# TMS320F280049CPZS.net
KiCad netlist of a schematic drawn in Altium Designer
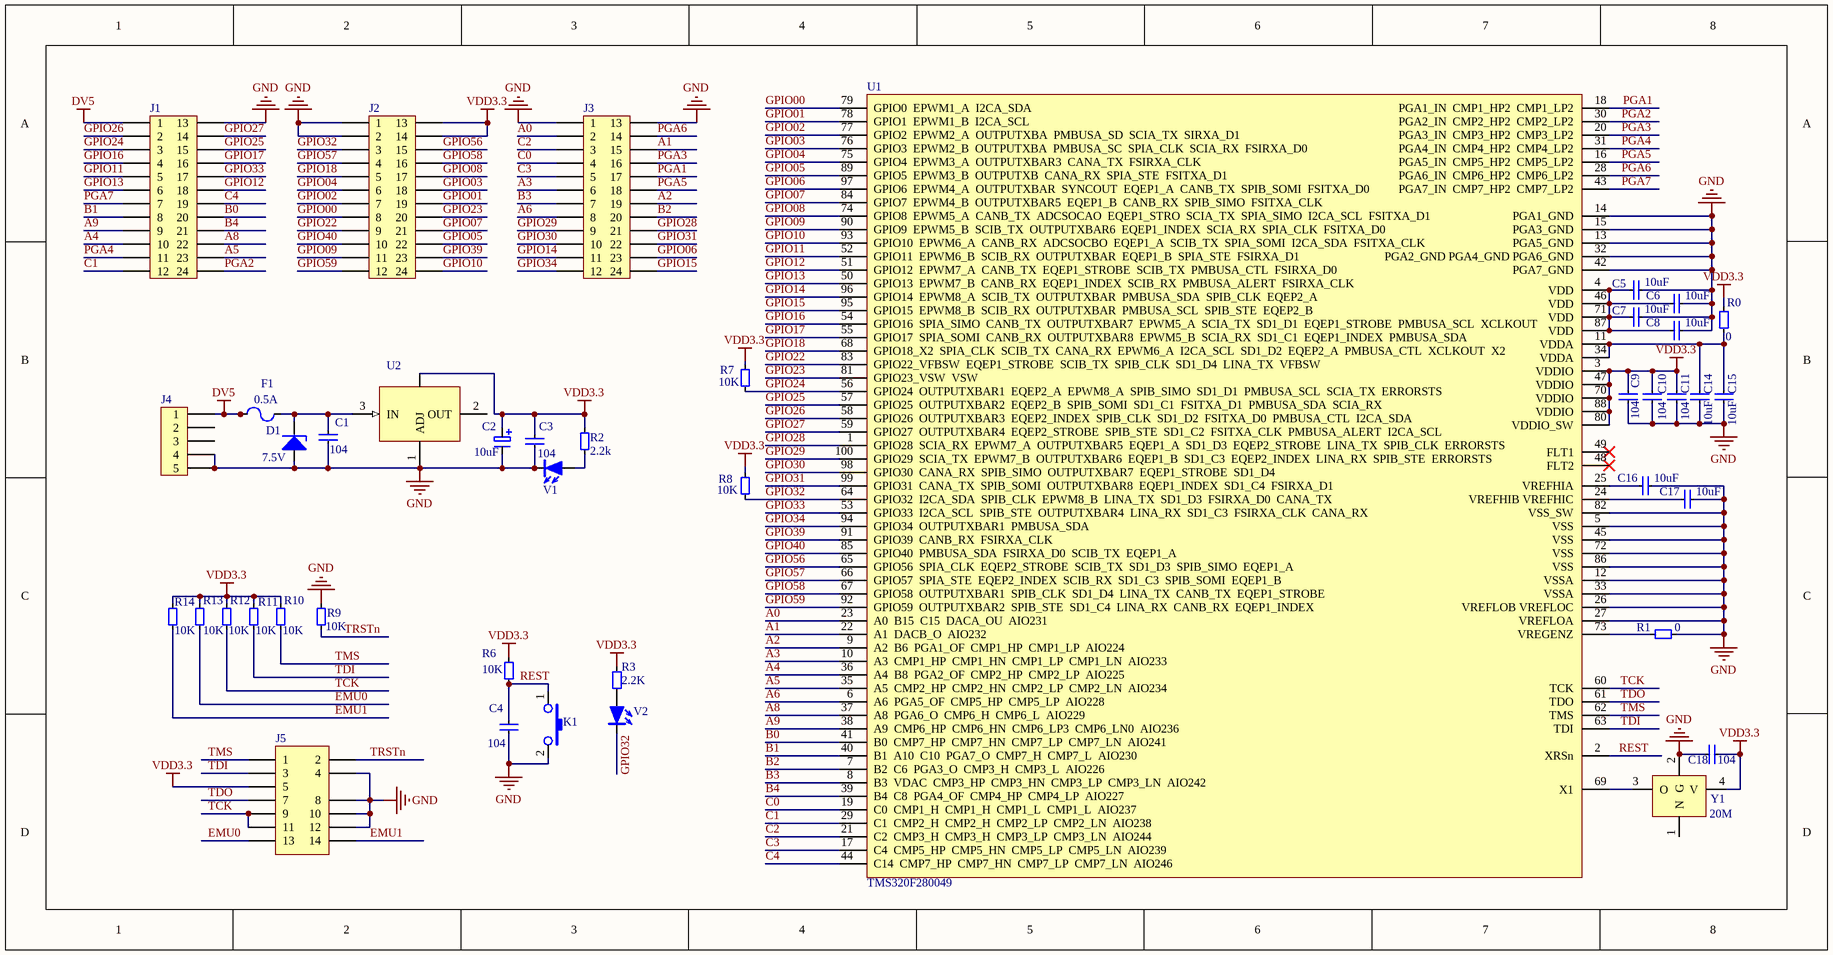
[diagram p0: TMS320F280049CPZS.SchDoc]

(export (version "E")
  (design (tool "Eeschema 10.0.6"))
  (components
    (comp (ref "C1") (value "104") (footprint "0805_C_M") (libsource (lib "电容系列") (part "C3")))
    (comp (ref "C2") (value "10uF") (footprint "CE3528") (libsource (lib "电容系列") (part "E3")))
    (comp (ref "C3") (value "104") (footprint "0805_C_M") (libsource (lib "电容系列") (part "C3")))
    (comp (ref "C4") (value "104") (footprint "0805_C_M") (libsource (lib "电容系列") (part "C3")))
    (comp (ref "C5") (value "10uF") (footprint "0805_C_M") (libsource (lib "电容系列") (part "C3")))
    (comp (ref "C6") (value "10uF") (footprint "0805_C_M") (libsource (lib "电容系列") (part "C3")))
    (comp (ref "C7") (value "10uF") (footprint "0805_C_M") (libsource (lib "电容系列") (part "C3")))
    (comp (ref "C8") (value "10uF") (footprint "0805_C_M") (libsource (lib "电容系列") (part "C3")))
    (comp (ref "C9") (value "104") (footprint "0805_C_M") (libsource (lib "电容系列") (part "C3")))
    (comp (ref "C10") (value "104") (footprint "0805_C_M") (libsource (lib "电容系列") (part "C3")))
    (comp (ref "C11") (value "104") (footprint "0805_C_M") (libsource (lib "电容系列") (part "C3")))
    (comp (ref "C14") (value "10uF") (footprint "0805_C_M") (libsource (lib "电容系列") (part "C3")))
    (comp (ref "C15") (value "10uF") (footprint "0805_C_M") (libsource (lib "电容系列") (part "C3")))
    (comp (ref "C16") (value "10uF") (footprint "0805_C_M") (libsource (lib "电容系列") (part "C3")))
    (comp (ref "C17") (value "10uF") (footprint "0805_C_M") (libsource (lib "电容系列") (part "C3")))
    (comp (ref "C18") (value "104") (footprint "0805_C_M") (libsource (lib "电容系列") (part "C3")))
    (comp (ref "D1") (value "7.5V") (footprint "1206D") (libsource (lib "二极管") (part "D4")))
    (comp (ref "F1") (value "0.5A") (footprint "1812F") (libsource (lib "常用库") (part "FUSE1")))
    (comp (ref "J1") (value "CON24") (footprint "CON24_2.54") (libsource (lib "DIP_SIP") (part "CON24")))
    (comp (ref "J2") (value "CON24") (footprint "CON24_2.54") (libsource (lib "DIP_SIP") (part "CON24")))
    (comp (ref "J3") (value "CON24") (footprint "CON24_2.54") (libsource (lib "DIP_SIP") (part "CON24")))
    (comp (ref "J4") (value "SIP5") (footprint "MINIUSB-S") (libsource (lib "DIP_SIP") (part "SIP5")))
    (comp (ref "J5")
      (value "Header 7X2")
      (footprint "JTAG14")
      (description "Header, 7-Pin, Dual row")
      (fields (field (name "PUBLISHER") "Altium Limited"))
      (libsource (lib "myproject") (part "Header 7X2"))
    )
    (comp (ref "K1") (value "KEY1") (libsource (lib "Common") (part "KEY1")))
    (comp (ref "R0") (value "0") (footprint "0805_R_M") (libsource (lib "电阻系列") (part "R3")))
    (comp (ref "R1") (value "0") (footprint "0805_R_M") (libsource (lib "电阻系列") (part "R3")))
    (comp (ref "R2") (value "2.2k") (footprint "0805_R_M") (libsource (lib "电阻系列") (part "R3")))
    (comp (ref "R3") (value "2.2K") (footprint "0805_R_M") (libsource (lib "电阻系列") (part "R3")))
    (comp (ref "R6") (value "10K") (footprint "0805_R_M") (libsource (lib "电阻系列") (part "R3")))
    (comp (ref "R7") (value "10K") (footprint "0805_R_M") (libsource (lib "电阻系列") (part "R3")))
    (comp (ref "R8") (value "10K") (footprint "0805_R_M") (libsource (lib "电阻系列") (part "R3")))
    (comp (ref "R9") (value "10K") (footprint "0805_R_M") (libsource (lib "电阻系列") (part "R3")))
    (comp (ref "R10") (value "10K") (footprint "0805_R_M") (libsource (lib "电阻系列") (part "R3")))
    (comp (ref "R11") (value "10K") (footprint "0805_R_M") (libsource (lib "电阻系列") (part "R3")))
    (comp (ref "R12") (value "10K") (footprint "0805_R_M") (libsource (lib "电阻系列") (part "R3")))
    (comp (ref "R13") (value "10K") (footprint "0805_R_M") (libsource (lib "电阻系列") (part "R3")))
    (comp (ref "R14") (value "10K") (footprint "0805_R_M") (libsource (lib "电阻系列") (part "R3")))
    (comp (ref "U1")
      (value "TMS320F280049")
      (footprint "STM32F407VGT6")
      (libsource (lib "IC-ZB") (part "TMS320F280049"))
    )
    (comp (ref "U2") (value "AMS1117-3.3") (footprint "LM1117") (libsource (lib "电源（专用）") (part "1117")))
    (comp (ref "V1") (value "LED") (footprint "0805D") (libsource (lib "发光管、数码管") (part "LED2")))
    (comp (ref "V2") (value "LED2") (footprint "0805D") (libsource (lib "发光管、数码管") (part "LED2")))
    (comp (ref "Y1") (value "20M") (footprint "OSC5070") (libsource (lib "常用库") (part "CY2_有源")))
  )
  (nets
    (net (code "1") (name "/A0") (class "Default")
      (node (ref "J3") (pin "2") (pinfunction "2_2") (pintype "passive"))
      (node (ref "U1") (pin "23") (pinfunction "A0__B15__C15__DACA_OU__AIO231_23") (pintype "passive"))
    )
    (net (code "2") (name "/A1") (class "Default")
      (node (ref "J3") (pin "15") (pinfunction "15_15") (pintype "passive"))
      (node (ref "U1") (pin "22") (pinfunction "A1__DACB_O__AIO232_22") (pintype "passive"))
    )
    (net (code "3") (name "/A2") (class "Default")
      (node (ref "J3") (pin "19") (pinfunction "19_19") (pintype "passive"))
      (node (ref "U1") (pin "9") (pinfunction "A2__B6__PGA1_OF__CMP1_HP__CMP1_LP__AIO224_9") (pintype "passive"))
    )
    (net (code "4") (name "/A3") (class "Default")
      (node (ref "J3") (pin "6") (pinfunction "6_6") (pintype "passive"))
      (node (ref "U1") (pin "10") (pinfunction "A3__CMP1_HP__CMP1_HN__CMP1_LP__CMP1_LN__AIO233_10") (pintype "passive"))
    )
    (net (code "5") (name "/A4") (class "Default")
      (node (ref "J1") (pin "10") (pinfunction "10_10") (pintype "passive"))
      (node (ref "U1") (pin "36") (pinfunction "A4__B8__PGA2_OF__CMP2_HP__CMP2_LP__AIO225_36") (pintype "passive"))
    )
    (net (code "6") (name "/A5") (class "Default")
      (node (ref "J1") (pin "23") (pinfunction "23_23") (pintype "passive"))
      (node (ref "U1") (pin "35") (pinfunction "A5__CMP2_HP__CMP2_HN__CMP2_LP__CMP2_LN__AIO234_35") (pintype "passive"))
    )
    (net (code "7") (name "/A6") (class "Default")
      (node (ref "J3") (pin "8") (pinfunction "8_8") (pintype "passive"))
      (node (ref "U1") (pin "6") (pinfunction "A6__PGA5_OF__CMP5_HP__CMP5_LP__AIO228_6") (pintype "passive"))
    )
    (net (code "8") (name "/A8") (class "Default")
      (node (ref "J1") (pin "22") (pinfunction "22_22") (pintype "passive"))
      (node (ref "U1") (pin "37") (pinfunction "A8__PGA6_O__CMP6_H__CMP6_L__AIO229_37") (pintype "passive"))
    )
    (net (code "9") (name "/A9") (class "Default")
      (node (ref "J1") (pin "9") (pinfunction "9_9") (pintype "passive"))
      (node (ref "U1") (pin "38") (pinfunction "A9__CMP6_HP__CMP6_HN__CMP6_LP3__CMP6_LN0__AIO236_38") (pintype "passive"))
    )
    (net (code "10") (name "/B0") (class "Default")
      (node (ref "J1") (pin "20") (pinfunction "20_20") (pintype "passive"))
      (node (ref "U1") (pin "41") (pinfunction "B0__CMP7_HP__CMP7_HN__CMP7_LP__CMP7_LN__AIO241_41") (pintype "passive"))
    )
    (net (code "11") (name "/B1") (class "Default")
      (node (ref "J1") (pin "8") (pinfunction "8_8") (pintype "passive"))
      (node (ref "U1") (pin "40") (pinfunction "B1__A10__C10__PGA7_O__CMP7_H__CMP7_L__AIO230_40") (pintype "passive"))
    )
    (net (code "12") (name "/B2") (class "Default")
      (node (ref "J3") (pin "20") (pinfunction "20_20") (pintype "passive"))
      (node (ref "U1") (pin "7") (pinfunction "B2__C6__PGA3_O__CMP3_H__CMP3_L__AIO226_7") (pintype "passive"))
    )
    (net (code "13") (name "/B3") (class "Default")
      (node (ref "J3") (pin "7") (pinfunction "7_7") (pintype "passive"))
      (node (ref "U1") (pin "8") (pinfunction "B3__VDAC__CMP3_HP__CMP3_HN__CMP3_LP__CMP3_LN__AIO242_8") (pintype "passive"))
    )
    (net (code "14") (name "/B4") (class "Default")
      (node (ref "J1") (pin "21") (pinfunction "21_21") (pintype "passive"))
      (node (ref "U1") (pin "39") (pinfunction "B4__C8__PGA4_OF__CMP4_HP__CMP4_LP__AIO227_39") (pintype "passive"))
    )
    (net (code "15") (name "/C0") (class "Default")
      (node (ref "J3") (pin "4") (pinfunction "4_4") (pintype "passive"))
      (node (ref "U1") (pin "19") (pinfunction "C0__CMP1_H__CMP1_H__CMP1_L__CMP1_L__AIO237_19") (pintype "passive"))
    )
    (net (code "16") (name "/C1") (class "Default")
      (node (ref "J1") (pin "12") (pinfunction "12_12") (pintype "passive"))
      (node (ref "U1") (pin "29") (pinfunction "C1__CMP2_H__CMP2_H__CMP2_LP__CMP2_LN__AIO238_29") (pintype "passive"))
    )
    (net (code "17") (name "/C2") (class "Default")
      (node (ref "J3") (pin "3") (pinfunction "3_3") (pintype "passive"))
      (node (ref "U1") (pin "21") (pinfunction "C2__CMP3_H__CMP3_H__CMP3_LP__CMP3_LN__AIO244_21") (pintype "passive"))
    )
    (net (code "18") (name "/C3") (class "Default")
      (node (ref "J3") (pin "5") (pinfunction "5_5") (pintype "passive"))
      (node (ref "U1") (pin "17") (pinfunction "C4__CMP5_HP__CMP5_HN__CMP5_LP__CMP5_LN__AIO239_17") (pintype "passive"))
    )
    (net (code "19") (name "/C4") (class "Default")
      (node (ref "J1") (pin "19") (pinfunction "19_19") (pintype "passive"))
      (node (ref "U1") (pin "44") (pinfunction "C14__CMP7_HP__CMP7_HN__CMP7_LP__CMP7_LN__AIO246_44") (pintype "passive"))
    )
    (net (code "20") (name "/EMU0") (class "Default")
      (node (ref "J5") (pin "13") (pinfunction "13_13") (pintype "passive"))
      (node (ref "R13") (pin "1") (pinfunction "1_1") (pintype "passive"))
    )
    (net (code "21") (name "/EMU1") (class "Default")
      (node (ref "J5") (pin "14") (pinfunction "14_14") (pintype "passive"))
      (node (ref "R14") (pin "1") (pinfunction "1_1") (pintype "passive"))
    )
    (net (code "22") (name "/GPIO00") (class "Default")
      (node (ref "J2") (pin "8") (pinfunction "8_8") (pintype "passive"))
      (node (ref "U1") (pin "79") (pinfunction "GPIO0__EPWM1_A__I2CA_SDA_79") (pintype "passive"))
    )
    (net (code "23") (name "/GPIO01") (class "Default")
      (node (ref "J2") (pin "19") (pinfunction "19_19") (pintype "passive"))
      (node (ref "U1") (pin "78") (pinfunction "GPIO1__EPWM1_B__I2CA_SCL_78") (pintype "passive"))
    )
    (net (code "24") (name "/GPIO02") (class "Default")
      (node (ref "J2") (pin "7") (pinfunction "7_7") (pintype "passive"))
      (node (ref "U1") (pin "77") (pinfunction "GPIO2__EPWM2_A__OUTPUTXBA__PMBUSA_SD__SCIA_TX__SIRXA_D1_77") (pintype "passive"))
    )
    (net (code "25") (name "/GPIO03") (class "Default")
      (node (ref "J2") (pin "18") (pinfunction "18_18") (pintype "passive"))
      (node (ref "U1") (pin "76") (pinfunction "GPIO3__EPWM2_B__OUTPUTXBA__PMBUSA_SC__SPIA_CLK__SCIA_RX__FSIRXA_D0_76") (pintype "passive"))
    )
    (net (code "26") (name "/GPIO04") (class "Default")
      (node (ref "J2") (pin "6") (pinfunction "6_6") (pintype "passive"))
      (node (ref "U1") (pin "75") (pinfunction "GPIO4__EPWM3_A__OUTPUTXBAR3__CANA_TX__FSIRXA_CLK_75") (pintype "passive"))
    )
    (net (code "27") (name "/GPIO05") (class "Default")
      (node (ref "J2") (pin "22") (pinfunction "22_22") (pintype "passive"))
      (node (ref "U1") (pin "89") (pinfunction "GPIO5__EPWM3_B__OUTPUTXB__CANA_RX__SPIA_STE__FSITXA_D1_89") (pintype "passive"))
    )
    (net (code "28") (name "/GPIO06") (class "Default")
      (node (ref "J3") (pin "23") (pinfunction "23_23") (pintype "passive"))
      (node (ref "U1") (pin "97") (pinfunction "GPIO6__EPWM4_A__OUTPUTXBAR__SYNCOUT__EQEP1_A__CANB_TX__SPIB_SOMI__FSITXA_D0_97") (pintype "passive"))
    )
    (net (code "29") (name "/GPIO07") (class "Default")
      (node (ref "J2") (pin "21") (pinfunction "21_21") (pintype "passive"))
      (node (ref "U1") (pin "84") (pinfunction "GPIO7__EPWM4_B__OUTPUTXBAR5__EQEP1_B__CANB_RX__SPIB_SIMO__FSITXA_CLK_84") (pintype "passive"))
    )
    (net (code "30") (name "/GPIO08") (class "Default")
      (node (ref "J2") (pin "17") (pinfunction "17_17") (pintype "passive"))
      (node (ref "U1") (pin "74") (pinfunction "GPIO8__EPWM5_A__CANB_TX__ADCSOCAO__EQEP1_STRO__SCIA_TX__SPIA_SIMO__I2CA_SCL__FSITXA_D1_74") (pintype "passive"))
    )
    (net (code "31") (name "/GPIO09") (class "Default")
      (node (ref "J2") (pin "11") (pinfunction "11_11") (pintype "passive"))
      (node (ref "U1") (pin "90") (pinfunction "GPIO9__EPWM5_B__SCIB_TX__OUTPUTXBAR6__EQEP1_INDEX__SCIA_RX__SPIA_CLK__FSITXA_D0_90") (pintype "passive"))
    )
    (net (code "32") (name "/GPIO10") (class "Default")
      (node (ref "J2") (pin "24") (pinfunction "24_24") (pintype "passive"))
      (node (ref "U1") (pin "93") (pinfunction "GPIO10__EPWM6_A__CANB_RX__ADCSOCBO__EQEP1_A__SCIB_TX__SPIA_SOMI__I2CA_SDA__FSITXA_CLK_93") (pintype "passive"))
    )
    (net (code "33") (name "/GPIO11") (class "Default")
      (node (ref "J1") (pin "5") (pinfunction "5_5") (pintype "passive"))
      (node (ref "U1") (pin "52") (pinfunction "GPIO11__EPWM6_B__SCIB_RX__OUTPUTXBAR__EQEP1_B__SPIA_STE__FSIRXA_D1_52") (pintype "passive"))
    )
    (net (code "34") (name "/GPIO12") (class "Default")
      (node (ref "J1") (pin "18") (pinfunction "18_18") (pintype "passive"))
      (node (ref "U1") (pin "51") (pinfunction "GPIO12__EPWM7_A__CANB_TX__EQEP1_STROBE__SCIB_TX__PMBUSA_CTL__FSIRXA_D0_51") (pintype "passive"))
    )
    (net (code "35") (name "/GPIO13") (class "Default")
      (node (ref "J1") (pin "6") (pinfunction "6_6") (pintype "passive"))
      (node (ref "U1") (pin "50") (pinfunction "GPIO13__EPWM7_B__CANB_RX__EQEP1_INDEX__SCIB_RX__PMBUSA_ALERT__FSIRXA_CLK_50") (pintype "passive"))
    )
    (net (code "36") (name "/GPIO14") (class "Default")
      (node (ref "J3") (pin "11") (pinfunction "11_11") (pintype "passive"))
      (node (ref "U1") (pin "96") (pinfunction "GPIO14__EPWM8_A__SCIB_TX__OUTPUTXBAR__PMBUSA_SDA__SPIB_CLK__EQEP2_A_96") (pintype "passive"))
    )
    (net (code "37") (name "/GPIO15") (class "Default")
      (node (ref "J3") (pin "24") (pinfunction "24_24") (pintype "passive"))
      (node (ref "U1") (pin "95") (pinfunction "GPIO15__EPWM8_B__SCIB_RX__OUTPUTXBAR__PMBUSA_SCL__SPIB_STE__EQEP2_B_95") (pintype "passive"))
    )
    (net (code "38") (name "/GPIO16") (class "Default")
      (node (ref "J1") (pin "4") (pinfunction "4_4") (pintype "passive"))
      (node (ref "U1") (pin "54") (pinfunction "GPIO16__SPIA_SIMO__CANB_TX__OUTPUTXBAR7__EPWM5_A__SCIA_TX__SD1_D1__EQEP1_STROBE__PMBUSA_SCL__XCLKOUT_54") (pintype "passive"))
    )
    (net (code "39") (name "/GPIO17") (class "Default")
      (node (ref "J1") (pin "16") (pinfunction "16_16") (pintype "passive"))
      (node (ref "U1") (pin "55") (pinfunction "GPIO17__SPIA_SOMI__CANB_RX__OUTPUTXBAR8__EPWM5_B__SCIA_RX__SD1_C1__EQEP1_INDEX__PMBUSA_SDA_55") (pintype "passive"))
    )
    (net (code "40") (name "/GPIO18") (class "Default")
      (node (ref "J2") (pin "5") (pinfunction "5_5") (pintype "passive"))
      (node (ref "U1") (pin "68") (pinfunction "GPIO18_X2__SPIA_CLK__SCIB_TX__CANA_RX__EPWM6_A__I2CA_SCL__SD1_D2__EQEP2_A__PMBUSA_CTL__XCLKOUT__X2_68") (pintype "passive"))
    )
    (net (code "41") (name "/GPIO22") (class "Default")
      (node (ref "J2") (pin "9") (pinfunction "9_9") (pintype "passive"))
      (node (ref "U1") (pin "83") (pinfunction "GPIO22_VFBSW__EQEP1_STROBE__SCIB_TX__SPIB_CLK__SD1_D4__LINA_TX__VFBSW_83") (pintype "passive"))
    )
    (net (code "42") (name "/GPIO23") (class "Default")
      (node (ref "J2") (pin "20") (pinfunction "20_20") (pintype "passive"))
      (node (ref "U1") (pin "81") (pinfunction "GPIO23_VSW__VSW_81") (pintype "passive"))
    )
    (net (code "43") (name "/GPIO24") (class "Default")
      (node (ref "J1") (pin "3") (pinfunction "3_3") (pintype "passive"))
      (node (ref "R7") (pin "1") (pinfunction "1_1") (pintype "passive"))
      (node (ref "U1") (pin "56") (pinfunction "GPIO24__OUTPUTXBAR1__EQEP2_A__EPWM8_A__SPIB_SIMO__SD1_D1__PMBUSA_SCL__SCIA_TX__ERRORSTS_56") (pintype "passive"))
    )
    (net (code "44") (name "/GPIO25") (class "Default")
      (node (ref "J1") (pin "15") (pinfunction "15_15") (pintype "passive"))
      (node (ref "U1") (pin "57") (pinfunction "GPIO25__OUTPUTXBAR2__EQEP2_B__SPIB_SOMI__SD1_C1__FSITXA_D1__PMBUSA_SDA__SCIA_RX_57") (pintype "passive"))
    )
    (net (code "45") (name "/GPIO26") (class "Default")
      (node (ref "J1") (pin "2") (pinfunction "2_2") (pintype "passive"))
      (node (ref "U1") (pin "58") (pinfunction "GPIO26__OUTPUTXBAR3__EQEP2_INDEX__SPIB_CLK__SD1_D2__FSITXA_D0__PMBUSA_CTL__I2CA_SDA_58") (pintype "passive"))
    )
    (net (code "46") (name "/GPIO27") (class "Default")
      (node (ref "J1") (pin "14") (pinfunction "14_14") (pintype "passive"))
      (node (ref "U1") (pin "59") (pinfunction "GPIO27__OUTPUTXBAR4__EQEP2_STROBE__SPIB_STE__SD1_C2__FSITXA_CLK__PMBUSA_ALERT__I2CA_SCL_59") (pintype "passive"))
    )
    (net (code "47") (name "/GPIO28") (class "Default")
      (node (ref "J3") (pin "21") (pinfunction "21_21") (pintype "passive"))
      (node (ref "U1") (pin "1") (pinfunction "GPIO28__SCIA_RX__EPWM7_A__OUTPUTXBAR5__EQEP1_A__SD1_D3__EQEP2_STROBE__LINA_TX__SPIB_CLK__ERRORSTS_1") (pintype "passive"))
    )
    (net (code "48") (name "/GPIO29") (class "Default")
      (node (ref "J3") (pin "9") (pinfunction "9_9") (pintype "passive"))
      (node (ref "U1") (pin "100") (pinfunction "GPIO29__SCIA_TX__EPWM7_B__OUTPUTXBAR6__EQEP1_B__SD1_C3__EQEP2_INDEX__LINA_RX__SPIB_STE__ERRORSTS_100") (pintype "passive"))
    )
    (net (code "49") (name "/GPIO30") (class "Default")
      (node (ref "J3") (pin "10") (pinfunction "10_10") (pintype "passive"))
      (node (ref "U1") (pin "98") (pinfunction "GPIO30__CANA_RX__SPIB_SIMO__OUTPUTXBAR7__EQEP1_STROBE__SD1_D4_98") (pintype "passive"))
    )
    (net (code "50") (name "/GPIO31") (class "Default")
      (node (ref "J3") (pin "22") (pinfunction "22_22") (pintype "passive"))
      (node (ref "U1") (pin "99") (pinfunction "GPIO31__CANA_TX__SPIB_SOMI__OUTPUTXBAR8__EQEP1_INDEX__SD1_C4__FSIRXA_D1_99") (pintype "passive"))
    )
    (net (code "51") (name "/GPIO32") (class "Default")
      (node (ref "J2") (pin "3") (pinfunction "3_3") (pintype "passive"))
      (node (ref "R8") (pin "2") (pinfunction "2_2") (pintype "passive"))
      (node (ref "U1") (pin "64") (pinfunction "GPIO32__I2CA_SDA__SPIB_CLK__EPWM8_B__LINA_TX__SD1_D3__FSIRXA_D0__CANA_TX_64") (pintype "passive"))
      (node (ref "V2") (pin "2") (pinfunction "2_2") (pintype "passive"))
    )
    (net (code "52") (name "/GPIO33") (class "Default")
      (node (ref "J1") (pin "17") (pinfunction "17_17") (pintype "passive"))
      (node (ref "U1") (pin "53") (pinfunction "GPIO33__I2CA_SCL__SPIB_STE__OUTPUTXBAR4__LINA_RX__SD1_C3__FSIRXA_CLK__CANA_RX_53") (pintype "passive"))
    )
    (net (code "53") (name "/GPIO34") (class "Default")
      (node (ref "J3") (pin "12") (pinfunction "12_12") (pintype "passive"))
      (node (ref "U1") (pin "94") (pinfunction "GPIO34__OUTPUTXBAR1__PMBUSA_SDA_94") (pintype "passive"))
    )
    (net (code "54") (name "/GPIO39") (class "Default")
      (node (ref "J2") (pin "23") (pinfunction "23_23") (pintype "passive"))
      (node (ref "U1") (pin "91") (pinfunction "GPIO39__CANB_RX__FSIRXA_CLK_91") (pintype "passive"))
    )
    (net (code "55") (name "/GPIO40") (class "Default")
      (node (ref "J2") (pin "10") (pinfunction "10_10") (pintype "passive"))
      (node (ref "U1") (pin "85") (pinfunction "GPIO40__PMBUSA_SDA__FSIRXA_D0__SCIB_TX__EQEP1_A_85") (pintype "passive"))
    )
    (net (code "56") (name "/GPIO56") (class "Default")
      (node (ref "J2") (pin "15") (pinfunction "15_15") (pintype "passive"))
      (node (ref "U1") (pin "65") (pinfunction "GPIO56__SPIA_CLK__EQEP2_STROBE__SCIB_TX__SD1_D3__SPIB_SIMO__EQEP1_A_65") (pintype "passive"))
    )
    (net (code "57") (name "/GPIO57") (class "Default")
      (node (ref "J2") (pin "4") (pinfunction "4_4") (pintype "passive"))
      (node (ref "U1") (pin "66") (pinfunction "GPIO57__SPIA_STE__EQEP2_INDEX__SCIB_RX__SD1_C3__SPIB_SOMI__EQEP1_B_66") (pintype "passive"))
    )
    (net (code "58") (name "/GPIO58") (class "Default")
      (node (ref "J2") (pin "16") (pinfunction "16_16") (pintype "passive"))
      (node (ref "U1") (pin "67") (pinfunction "GPIO58__OUTPUTXBAR1__SPIB_CLK__SD1_D4__LINA_TX__CANB_TX__EQEP1_STROBE_67") (pintype "passive"))
    )
    (net (code "59") (name "/GPIO59") (class "Default")
      (node (ref "J2") (pin "12") (pinfunction "12_12") (pintype "passive"))
      (node (ref "U1") (pin "92") (pinfunction "GPIO59__OUTPUTXBAR2__SPIB_STE__SD1_C4__LINA_RX__CANB_RX__EQEP1_INDEX_92") (pintype "passive"))
    )
    (net (code "60") (name "/PGA1") (class "Default")
      (node (ref "J3") (pin "17") (pinfunction "17_17") (pintype "passive"))
      (node (ref "U1") (pin "18") (pinfunction "PGA1_IN__CMP1_HP2__CMP1_LP2_18") (pintype "passive"))
    )
    (net (code "61") (name "/PGA2") (class "Default")
      (node (ref "J1") (pin "24") (pinfunction "24_24") (pintype "passive"))
      (node (ref "U1") (pin "30") (pinfunction "PGA2_IN__CMP2_HP2__CMP2_LP2_30") (pintype "passive"))
    )
    (net (code "62") (name "/PGA3") (class "Default")
      (node (ref "J3") (pin "16") (pinfunction "16_16") (pintype "passive"))
      (node (ref "U1") (pin "20") (pinfunction "PGA3_IN__CMP3_HP2__CMP3_LP2_20") (pintype "passive"))
    )
    (net (code "63") (name "/PGA4") (class "Default")
      (node (ref "J1") (pin "11") (pinfunction "11_11") (pintype "passive"))
      (node (ref "U1") (pin "31") (pinfunction "PGA4_IN__CMP4_HP2__CMP4_LP2_31") (pintype "passive"))
    )
    (net (code "64") (name "/PGA5") (class "Default")
      (node (ref "J3") (pin "18") (pinfunction "18_18") (pintype "passive"))
      (node (ref "U1") (pin "16") (pinfunction "PGA5_IN__CMP5_HP2__CMP5_LP2_16") (pintype "passive"))
    )
    (net (code "65") (name "/PGA6") (class "Default")
      (node (ref "J3") (pin "14") (pinfunction "14_14") (pintype "passive"))
      (node (ref "U1") (pin "28") (pinfunction "PGA6_IN__CMP6_HP2__CMP6_LP2_28") (pintype "passive"))
    )
    (net (code "66") (name "/PGA7") (class "Default")
      (node (ref "J1") (pin "7") (pinfunction "7_7") (pintype "passive"))
      (node (ref "U1") (pin "43") (pinfunction "PGA7_IN__CMP7_HP2__CMP7_LP2_43") (pintype "passive"))
    )
    (net (code "67") (name "/REST") (class "Default")
      (node (ref "C4") (pin "2") (pinfunction "2_2") (pintype "passive"))
      (node (ref "K1") (pin "1") (pintype "passive"))
      (node (ref "R6") (pin "2") (pinfunction "2_2") (pintype "passive"))
      (node (ref "U1") (pin "2") (pinfunction "XRSn_2") (pintype "passive"))
    )
    (net (code "68") (name "/TCK") (class "Default")
      (node (ref "J5") (pin "11") (pinfunction "11_11") (pintype "passive"))
      (node (ref "J5") (pin "9") (pinfunction "9_9") (pintype "passive"))
      (node (ref "R12") (pin "1") (pinfunction "1_1") (pintype "passive"))
      (node (ref "U1") (pin "60") (pinfunction "TCK_60") (pintype "passive"))
    )
    (net (code "69") (name "/TDI") (class "Default")
      (node (ref "J5") (pin "3") (pinfunction "3_3") (pintype "passive"))
      (node (ref "R11") (pin "1") (pinfunction "1_1") (pintype "passive"))
      (node (ref "U1") (pin "63") (pinfunction "TDI_63") (pintype "passive"))
    )
    (net (code "70") (name "/TDO") (class "Default")
      (node (ref "J5") (pin "7") (pinfunction "7_7") (pintype "passive"))
      (node (ref "U1") (pin "61") (pinfunction "TDO_61") (pintype "passive"))
    )
    (net (code "71") (name "/TMS") (class "Default")
      (node (ref "J5") (pin "1") (pinfunction "1_1") (pintype "passive"))
      (node (ref "R10") (pin "1") (pinfunction "1_1") (pintype "passive"))
      (node (ref "U1") (pin "62") (pinfunction "TMS_62") (pintype "passive"))
    )
    (net (code "72") (name "/TRSTn") (class "Default")
      (node (ref "J5") (pin "2") (pinfunction "2_2") (pintype "passive"))
      (node (ref "R9") (pin "1") (pinfunction "1_1") (pintype "passive"))
    )
    (net (code "73") (name "DV5") (class "Default")
      (node (ref "F1") (pin "1") (pintype "input"))
      (node (ref "J1") (pin "1") (pinfunction "1_1") (pintype "passive"))
      (node (ref "J4") (pin "1") (pinfunction "1_1") (pintype "passive"))
    )
    (net (code "74") (name "GND") (class "Default")
      (node (ref "C1") (pin "2") (pinfunction "2_2") (pintype "passive"))
      (node (ref "C10") (pin "2") (pinfunction "2_2") (pintype "passive"))
      (node (ref "C11") (pin "2") (pinfunction "2_2") (pintype "passive"))
      (node (ref "C14") (pin "2") (pinfunction "2_2") (pintype "passive"))
      (node (ref "C15") (pin "2") (pinfunction "2_2") (pintype "passive"))
      (node (ref "C16") (pin "2") (pinfunction "2_2") (pintype "passive"))
      (node (ref "C17") (pin "2") (pinfunction "2_2") (pintype "passive"))
      (node (ref "C18") (pin "1") (pinfunction "1_1") (pintype "passive"))
      (node (ref "C2") (pin "2") (pinfunction "2_2") (pintype "passive"))
      (node (ref "C3") (pin "2") (pinfunction "2_2") (pintype "passive"))
      (node (ref "C4") (pin "1") (pinfunction "1_1") (pintype "passive"))
      (node (ref "C5") (pin "2") (pinfunction "2_2") (pintype "passive"))
      (node (ref "C6") (pin "2") (pinfunction "2_2") (pintype "passive"))
      (node (ref "C7") (pin "2") (pinfunction "2_2") (pintype "passive"))
      (node (ref "C8") (pin "2") (pinfunction "2_2") (pintype "passive"))
      (node (ref "C9") (pin "2") (pinfunction "2_2") (pintype "passive"))
      (node (ref "D1") (pin "1") (pinfunction "1_1") (pintype "passive"))
      (node (ref "J1") (pin "13") (pinfunction "13_13") (pintype "passive"))
      (node (ref "J2") (pin "1") (pinfunction "1_1") (pintype "passive"))
      (node (ref "J2") (pin "2") (pinfunction "2_2") (pintype "passive"))
      (node (ref "J3") (pin "1") (pinfunction "1_1") (pintype "passive"))
      (node (ref "J3") (pin "13") (pinfunction "13_13") (pintype "passive"))
      (node (ref "J4") (pin "4") (pinfunction "4_4") (pintype "passive"))
      (node (ref "J4") (pin "5") (pinfunction "5_5") (pintype "passive"))
      (node (ref "J5") (pin "10") (pinfunction "10_10") (pintype "passive"))
      (node (ref "J5") (pin "12") (pinfunction "12_12") (pintype "passive"))
      (node (ref "J5") (pin "4") (pinfunction "4_4") (pintype "passive"))
      (node (ref "J5") (pin "8") (pinfunction "8_8") (pintype "passive"))
      (node (ref "K1") (pin "2") (pintype "passive"))
      (node (ref "R1") (pin "2") (pinfunction "2_2") (pintype "passive"))
      (node (ref "R9") (pin "2") (pinfunction "2_2") (pintype "passive"))
      (node (ref "U1") (pin "12") (pinfunction "VSSA_12") (pintype "passive"))
      (node (ref "U1") (pin "13") (pinfunction "PGA5_GND_13") (pintype "passive"))
      (node (ref "U1") (pin "14") (pinfunction "PGA1_GND_14") (pintype "passive"))
      (node (ref "U1") (pin "15") (pinfunction "PGA3_GND_15") (pintype "passive"))
      (node (ref "U1") (pin "26") (pinfunction "VREFLOB_VREFLOC_26") (pintype "passive"))
      (node (ref "U1") (pin "27") (pinfunction "VREFLOA_27") (pintype "passive"))
      (node (ref "U1") (pin "32") (pinfunction "PGA2_GND_PGA4_GND_PGA6_GND_32") (pintype "passive"))
      (node (ref "U1") (pin "33") (pinfunction "VSSA_33") (pintype "passive"))
      (node (ref "U1") (pin "42") (pinfunction "PGA7_GND_42") (pintype "passive"))
      (node (ref "U1") (pin "45") (pinfunction "VSS_45") (pintype "passive"))
      (node (ref "U1") (pin "5") (pinfunction "VSS_5") (pintype "passive"))
      (node (ref "U1") (pin "72") (pinfunction "VSS_72") (pintype "passive"))
      (node (ref "U1") (pin "82") (pinfunction "VSS_SW_82") (pintype "passive"))
      (node (ref "U1") (pin "86") (pinfunction "VSS_86") (pintype "passive"))
      (node (ref "U2") (pin "1") (pinfunction "ADJ_1") (pintype "power_in"))
      (node (ref "V1") (pin "2") (pinfunction "2_2") (pintype "passive"))
      (node (ref "Y1") (pin "2") (pinfunction "G_2") (pintype "passive"))
    )
    (net (code "75") (name "Net-(C5-Pad1)") (class "Default")
      (node (ref "C5") (pin "1") (pinfunction "1_1") (pintype "passive"))
      (node (ref "C6") (pin "1") (pinfunction "1_1") (pintype "passive"))
      (node (ref "C7") (pin "1") (pinfunction "1_1") (pintype "passive"))
      (node (ref "C8") (pin "1") (pinfunction "1_1") (pintype "passive"))
      (node (ref "U1") (pin "4") (pinfunction "VDD_4") (pintype "passive"))
      (node (ref "U1") (pin "46") (pinfunction "VDD_46") (pintype "passive"))
      (node (ref "U1") (pin "71") (pinfunction "VDD_71") (pintype "passive"))
      (node (ref "U1") (pin "87") (pinfunction "VDD_87") (pintype "passive"))
    )
    (net (code "76") (name "Net-(C14-Pad1)") (class "Default")
      (node (ref "C14") (pin "1") (pinfunction "1_1") (pintype "passive"))
      (node (ref "C15") (pin "1") (pinfunction "1_1") (pintype "passive"))
      (node (ref "R0") (pin "1") (pinfunction "1_1") (pintype "passive"))
      (node (ref "U1") (pin "11") (pinfunction "VDDA_11") (pintype "passive"))
      (node (ref "U1") (pin "34") (pinfunction "VDDA_34") (pintype "passive"))
    )
    (net (code "77") (name "Net-(R2-Pad2)") (class "Default")
      (node (ref "R2") (pin "2") (pinfunction "2_2") (pintype "passive"))
      (node (ref "V1") (pin "1") (pinfunction "1_1") (pintype "passive"))
    )
    (net (code "78") (name "Net-(R3-Pad2)") (class "Default")
      (node (ref "R3") (pin "2") (pinfunction "2_2") (pintype "passive"))
      (node (ref "V2") (pin "1") (pinfunction "1_1") (pintype "passive"))
    )
    (net (code "79") (name "Net-(U1-VREFHIA)") (class "Default")
      (node (ref "C16") (pin "1") (pinfunction "1_1") (pintype "passive"))
      (node (ref "U1") (pin "25") (pinfunction "VREFHIA_25") (pintype "passive"))
    )
    (net (code "80") (name "Net-(U1-VREFHIB_VREFHIC)") (class "Default")
      (node (ref "C17") (pin "1") (pinfunction "1_1") (pintype "passive"))
      (node (ref "U1") (pin "24") (pinfunction "VREFHIB_VREFHIC_24") (pintype "passive"))
    )
    (net (code "81") (name "Net-(U1-VREGENZ)") (class "Default")
      (node (ref "R1") (pin "1") (pinfunction "1_1") (pintype "passive"))
      (node (ref "U1") (pin "73") (pinfunction "VREGENZ_73") (pintype "passive"))
    )
    (net (code "82") (name "Net-(U1-X1)") (class "Default")
      (node (ref "U1") (pin "69") (pinfunction "X1_69") (pintype "passive"))
      (node (ref "Y1") (pin "3") (pinfunction "O_3") (pintype "passive"))
    )
    (net (code "83") (name "Net-(U2-IN)") (class "Default")
      (node (ref "C1") (pin "1") (pinfunction "1_1") (pintype "passive"))
      (node (ref "D1") (pin "2") (pinfunction "2_2") (pintype "passive"))
      (node (ref "F1") (pin "2") (pintype "input"))
      (node (ref "U2") (pin "3") (pinfunction "IN_3") (pintype "input"))
    )
    (net (code "84") (name "VDD3.3") (class "Default")
      (node (ref "C10") (pin "1") (pinfunction "1_1") (pintype "passive"))
      (node (ref "C11") (pin "1") (pinfunction "1_1") (pintype "passive"))
      (node (ref "C18") (pin "2") (pinfunction "2_2") (pintype "passive"))
      (node (ref "C2") (pin "1") (pinfunction "1_1") (pintype "passive"))
      (node (ref "C3") (pin "1") (pinfunction "1_1") (pintype "passive"))
      (node (ref "C9") (pin "1") (pinfunction "1_1") (pintype "passive"))
      (node (ref "J2") (pin "13") (pinfunction "13_13") (pintype "passive"))
      (node (ref "J2") (pin "14") (pinfunction "14_14") (pintype "passive"))
      (node (ref "J5") (pin "5") (pinfunction "5_5") (pintype "passive"))
      (node (ref "R0") (pin "2") (pinfunction "2_2") (pintype "passive"))
      (node (ref "R10") (pin "2") (pinfunction "2_2") (pintype "passive"))
      (node (ref "R11") (pin "2") (pinfunction "2_2") (pintype "passive"))
      (node (ref "R12") (pin "2") (pinfunction "2_2") (pintype "passive"))
      (node (ref "R13") (pin "2") (pinfunction "2_2") (pintype "passive"))
      (node (ref "R14") (pin "2") (pinfunction "2_2") (pintype "passive"))
      (node (ref "R2") (pin "1") (pinfunction "1_1") (pintype "passive"))
      (node (ref "R3") (pin "1") (pinfunction "1_1") (pintype "passive"))
      (node (ref "R6") (pin "1") (pinfunction "1_1") (pintype "passive"))
      (node (ref "R7") (pin "2") (pinfunction "2_2") (pintype "passive"))
      (node (ref "R8") (pin "1") (pinfunction "1_1") (pintype "passive"))
      (node (ref "U1") (pin "3") (pinfunction "VDDIO_3") (pintype "passive"))
      (node (ref "U1") (pin "47") (pinfunction "VDDIO_47") (pintype "passive"))
      (node (ref "U1") (pin "70") (pinfunction "VDDIO_70") (pintype "passive"))
      (node (ref "U1") (pin "80") (pinfunction "VDDIO_SW_80") (pintype "passive"))
      (node (ref "U1") (pin "88") (pinfunction "VDDIO_88") (pintype "passive"))
      (node (ref "U2") (pin "4") (pintype "passive"))
      (node (ref "Y1") (pin "4") (pinfunction "V_4") (pintype "passive"))
    )
    (net (code "85") (name "unconnected-(J4-Pad2)") (class "Default")
      (node (ref "J4") (pin "2") (pinfunction "2_2") (pintype "passive"))
    )
    (net (code "86") (name "unconnected-(J4-Pad3)") (class "Default")
      (node (ref "J4") (pin "3") (pinfunction "3_3") (pintype "passive"))
    )
    (net (code "87") (name "unconnected-(U1-FLT1-Pad49)") (class "Default")
      (node (ref "U1") (pin "49") (pinfunction "FLT1_49") (pintype "passive+no_connect"))
    )
    (net (code "88") (name "unconnected-(U1-FLT2-Pad48)") (class "Default")
      (node (ref "U1") (pin "48") (pinfunction "FLT2_48") (pintype "passive+no_connect"))
    )
    (net (code "89") (name "unconnected-(U2-OUT-Pad2)") (class "Default")
      (node (ref "U2") (pin "2") (pinfunction "OUT_2") (pintype "power_in"))
    )
    (net (code "90") (name "unconnected-(Y1-N-Pad1)") (class "Default")
      (node (ref "Y1") (pin "1") (pinfunction "N_1") (pintype "passive"))
    )
  )
)
